# Esquematico.net
KiCad netlist of a schematic drawn in Altium Designer
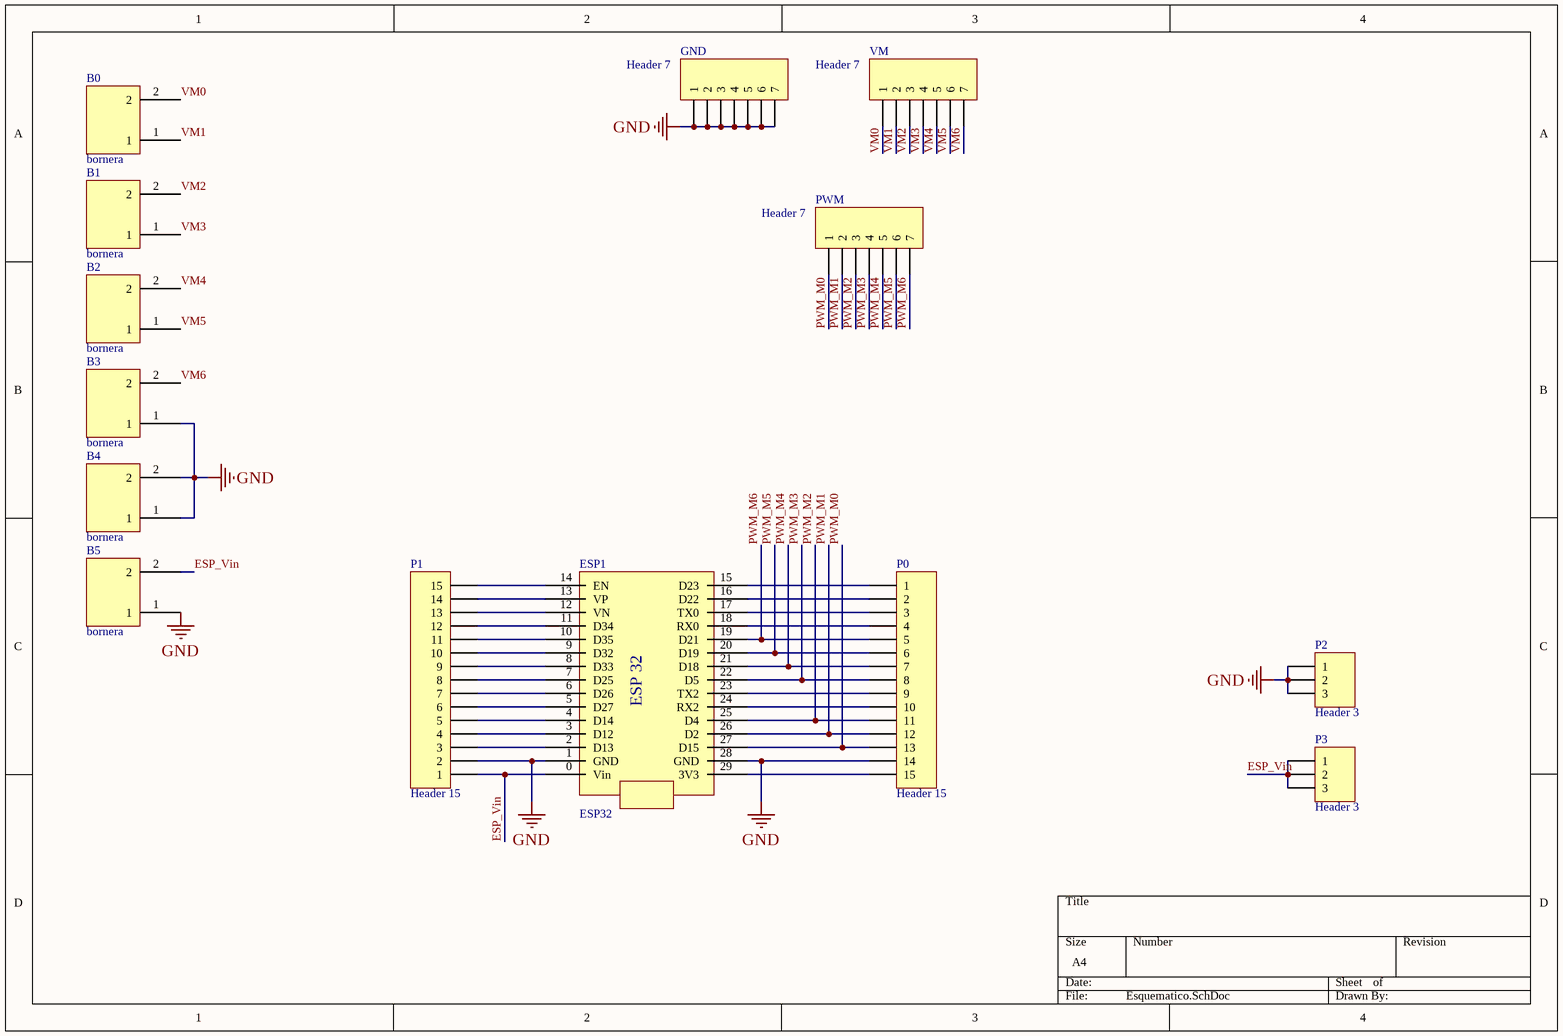
[diagram p0: Esquematico.SchDoc]

(export (version "E")
  (design (tool "Eeschema 10.0.6"))
  (components
    (comp (ref "B0") (value "bornera") (footprint "bornera chica") (libsource (lib "Erick") (part "bornera")))
    (comp (ref "B1") (value "bornera") (footprint "bornera chica") (libsource (lib "Erick") (part "bornera")))
    (comp (ref "B2") (value "bornera") (footprint "bornera chica") (libsource (lib "Erick") (part "bornera")))
    (comp (ref "B3") (value "bornera") (footprint "bornera chica") (libsource (lib "Erick") (part "bornera")))
    (comp (ref "B4") (value "bornera") (footprint "bornera chica") (libsource (lib "Erick") (part "bornera")))
    (comp (ref "B5") (value "bornera") (footprint "bornera chica") (libsource (lib "Erick") (part "bornera")))
    (comp (ref "ESP1") (value "ESP32") (footprint "ESP32") (libsource (lib "Erick") (part "ESP32")))
    (comp (ref "GND")
      (value "Header 7")
      (footprint "Header 7")
      (description "Header, 7-Pin")
      (fields (field (name "PUBLISHER") "Altium Limited"))
      (libsource (lib "hphonglib") (part "Header 7"))
    )
    (comp (ref "P0")
      (value "Header 15")
      (footprint "HDR1X15")
      (description "Header, 15-Pin")
      (fields (field (name "PUBLISHER") "Altium Limited"))
      (libsource (lib "") (part "Header 15_1"))
    )
    (comp (ref "P1")
      (value "Header 15")
      (footprint "HDR1X15")
      (description "Header, 15-Pin")
      (fields (field (name "PUBLISHER") "Altium Limited"))
      (libsource (lib "Miscellaneous Connectors") (part "Header 15"))
    )
    (comp (ref "P2")
      (value "Header 3")
      (footprint "Header 3")
      (description "Header, 3-Pin")
      (fields (field (name "PUBLISHER") "Altium Limited"))
      (libsource (lib "Miscellaneous Connectors") (part "Header 3"))
    )
    (comp (ref "P3")
      (value "Header 3")
      (footprint "Header 3")
      (description "Header, 3-Pin")
      (fields (field (name "PUBLISHER") "Altium Limited"))
      (libsource (lib "Miscellaneous Connectors") (part "Header 3"))
    )
    (comp (ref "PWM")
      (value "Header 7")
      (footprint "Header 7")
      (description "Header, 7-Pin")
      (fields (field (name "PUBLISHER") "Altium Limited"))
      (libsource (lib "hphonglib") (part "Header 7"))
    )
    (comp (ref "VM")
      (value "Header 7")
      (footprint "Header 7")
      (description "Header, 7-Pin")
      (fields (field (name "PUBLISHER") "Altium Limited"))
      (libsource (lib "hphonglib") (part "Header 7"))
    )
  )
  (nets
    (net (code "1") (name "/ESP_Vin") (class "Default")
      (node (ref "B5") (pin "2") (pinfunction "2_2") (pintype "passive"))
      (node (ref "ESP1") (pin "0") (pinfunction "Vin_0") (pintype "passive"))
      (node (ref "P1") (pin "1") (pinfunction "1_1") (pintype "passive"))
      (node (ref "P3") (pin "1") (pinfunction "1_1") (pintype "passive"))
      (node (ref "P3") (pin "2") (pinfunction "2_2") (pintype "passive"))
      (node (ref "P3") (pin "3") (pinfunction "3_3") (pintype "passive"))
    )
    (net (code "2") (name "/PWM_M0") (class "Default")
      (node (ref "ESP1") (pin "27") (pinfunction "D15_27") (pintype "passive"))
      (node (ref "P0") (pin "13") (pinfunction "13_13") (pintype "passive"))
      (node (ref "PWM") (pin "1") (pinfunction "1_1") (pintype "passive"))
    )
    (net (code "3") (name "/PWM_M1") (class "Default")
      (node (ref "ESP1") (pin "26") (pinfunction "D2_26") (pintype "passive"))
      (node (ref "P0") (pin "12") (pinfunction "12_12") (pintype "passive"))
      (node (ref "PWM") (pin "2") (pinfunction "2_2") (pintype "passive"))
    )
    (net (code "4") (name "/PWM_M2") (class "Default")
      (node (ref "ESP1") (pin "25") (pinfunction "D4_25") (pintype "passive"))
      (node (ref "P0") (pin "11") (pinfunction "11_11") (pintype "passive"))
      (node (ref "PWM") (pin "3") (pinfunction "3_3") (pintype "passive"))
    )
    (net (code "5") (name "/PWM_M3") (class "Default")
      (node (ref "ESP1") (pin "22") (pinfunction "D5_22") (pintype "passive"))
      (node (ref "P0") (pin "8") (pinfunction "8_8") (pintype "passive"))
      (node (ref "PWM") (pin "4") (pinfunction "4_4") (pintype "passive"))
    )
    (net (code "6") (name "/PWM_M4") (class "Default")
      (node (ref "ESP1") (pin "21") (pinfunction "D18_21") (pintype "passive"))
      (node (ref "P0") (pin "7") (pinfunction "7_7") (pintype "passive"))
      (node (ref "PWM") (pin "5") (pinfunction "5_5") (pintype "passive"))
    )
    (net (code "7") (name "/PWM_M5") (class "Default")
      (node (ref "ESP1") (pin "20") (pinfunction "D19_20") (pintype "passive"))
      (node (ref "P0") (pin "6") (pinfunction "6_6") (pintype "passive"))
      (node (ref "PWM") (pin "6") (pinfunction "6_6") (pintype "passive"))
    )
    (net (code "8") (name "/PWM_M6") (class "Default")
      (node (ref "ESP1") (pin "19") (pinfunction "D21_19") (pintype "passive"))
      (node (ref "P0") (pin "5") (pinfunction "5_5") (pintype "passive"))
      (node (ref "PWM") (pin "7") (pinfunction "7_7") (pintype "passive"))
    )
    (net (code "9") (name "/VM0") (class "Default")
      (node (ref "B0") (pin "2") (pinfunction "2_2") (pintype "passive"))
      (node (ref "VM") (pin "1") (pinfunction "1_1") (pintype "passive"))
    )
    (net (code "10") (name "/VM1") (class "Default")
      (node (ref "B0") (pin "1") (pinfunction "1_1") (pintype "passive"))
      (node (ref "VM") (pin "2") (pinfunction "2_2") (pintype "passive"))
    )
    (net (code "11") (name "/VM2") (class "Default")
      (node (ref "B1") (pin "2") (pinfunction "2_2") (pintype "passive"))
      (node (ref "VM") (pin "3") (pinfunction "3_3") (pintype "passive"))
    )
    (net (code "12") (name "/VM3") (class "Default")
      (node (ref "B1") (pin "1") (pinfunction "1_1") (pintype "passive"))
      (node (ref "VM") (pin "4") (pinfunction "4_4") (pintype "passive"))
    )
    (net (code "13") (name "/VM4") (class "Default")
      (node (ref "B2") (pin "2") (pinfunction "2_2") (pintype "passive"))
      (node (ref "VM") (pin "5") (pinfunction "5_5") (pintype "passive"))
    )
    (net (code "14") (name "/VM5") (class "Default")
      (node (ref "B2") (pin "1") (pinfunction "1_1") (pintype "passive"))
      (node (ref "VM") (pin "6") (pinfunction "6_6") (pintype "passive"))
    )
    (net (code "15") (name "/VM6") (class "Default")
      (node (ref "B3") (pin "2") (pinfunction "2_2") (pintype "passive"))
      (node (ref "VM") (pin "7") (pinfunction "7_7") (pintype "passive"))
    )
    (net (code "16") (name "GND") (class "Default")
      (node (ref "B3") (pin "1") (pinfunction "1_1") (pintype "passive"))
      (node (ref "B4") (pin "1") (pinfunction "1_1") (pintype "passive"))
      (node (ref "B4") (pin "2") (pinfunction "2_2") (pintype "passive"))
      (node (ref "B5") (pin "1") (pinfunction "1_1") (pintype "passive"))
      (node (ref "ESP1") (pin "1") (pinfunction "GND_1") (pintype "passive"))
      (node (ref "ESP1") (pin "28") (pinfunction "GND_28") (pintype "passive"))
      (node (ref "GND") (pin "1") (pinfunction "1_1") (pintype "passive"))
      (node (ref "GND") (pin "2") (pinfunction "2_2") (pintype "passive"))
      (node (ref "GND") (pin "3") (pinfunction "3_3") (pintype "passive"))
      (node (ref "GND") (pin "4") (pinfunction "4_4") (pintype "passive"))
      (node (ref "GND") (pin "5") (pinfunction "5_5") (pintype "passive"))
      (node (ref "GND") (pin "6") (pinfunction "6_6") (pintype "passive"))
      (node (ref "GND") (pin "7") (pinfunction "7_7") (pintype "passive"))
      (node (ref "P0") (pin "14") (pinfunction "14_14") (pintype "passive"))
      (node (ref "P1") (pin "2") (pinfunction "2_2") (pintype "passive"))
      (node (ref "P2") (pin "1") (pinfunction "1_1") (pintype "passive"))
      (node (ref "P2") (pin "2") (pinfunction "2_2") (pintype "passive"))
      (node (ref "P2") (pin "3") (pinfunction "3_3") (pintype "passive"))
    )
    (net (code "17") (name "Net-(ESP1-3V3)") (class "Default")
      (node (ref "ESP1") (pin "29") (pinfunction "3V3_29") (pintype "passive"))
      (node (ref "P0") (pin "15") (pinfunction "15_15") (pintype "passive"))
    )
    (net (code "18") (name "Net-(ESP1-D12)") (class "Default")
      (node (ref "ESP1") (pin "3") (pinfunction "D12_3") (pintype "passive"))
      (node (ref "P1") (pin "4") (pinfunction "4_4") (pintype "passive"))
    )
    (net (code "19") (name "Net-(ESP1-D13)") (class "Default")
      (node (ref "ESP1") (pin "2") (pinfunction "D13_2") (pintype "passive"))
      (node (ref "P1") (pin "3") (pinfunction "3_3") (pintype "passive"))
    )
    (net (code "20") (name "Net-(ESP1-D14)") (class "Default")
      (node (ref "ESP1") (pin "4") (pinfunction "D14_4") (pintype "passive"))
      (node (ref "P1") (pin "5") (pinfunction "5_5") (pintype "passive"))
    )
    (net (code "21") (name "Net-(ESP1-D22)") (class "Default")
      (node (ref "ESP1") (pin "16") (pinfunction "D22_16") (pintype "passive"))
      (node (ref "P0") (pin "2") (pinfunction "2_2") (pintype "passive"))
    )
    (net (code "22") (name "Net-(ESP1-D23)") (class "Default")
      (node (ref "ESP1") (pin "15") (pinfunction "D23_15") (pintype "passive"))
      (node (ref "P0") (pin "1") (pinfunction "1_1") (pintype "passive"))
    )
    (net (code "23") (name "Net-(ESP1-D25)") (class "Default")
      (node (ref "ESP1") (pin "7") (pinfunction "D25_7") (pintype "passive"))
      (node (ref "P1") (pin "8") (pinfunction "8_8") (pintype "passive"))
    )
    (net (code "24") (name "Net-(ESP1-D26)") (class "Default")
      (node (ref "ESP1") (pin "6") (pinfunction "D26_6") (pintype "passive"))
      (node (ref "P1") (pin "7") (pinfunction "7_7") (pintype "passive"))
    )
    (net (code "25") (name "Net-(ESP1-D27)") (class "Default")
      (node (ref "ESP1") (pin "5") (pinfunction "D27_5") (pintype "passive"))
      (node (ref "P1") (pin "6") (pinfunction "6_6") (pintype "passive"))
    )
    (net (code "26") (name "Net-(ESP1-D32)") (class "Default")
      (node (ref "ESP1") (pin "9") (pinfunction "D32_9") (pintype "passive"))
      (node (ref "P1") (pin "10") (pinfunction "10_10") (pintype "passive"))
    )
    (net (code "27") (name "Net-(ESP1-D33)") (class "Default")
      (node (ref "ESP1") (pin "8") (pinfunction "D33_8") (pintype "passive"))
      (node (ref "P1") (pin "9") (pinfunction "9_9") (pintype "passive"))
    )
    (net (code "28") (name "Net-(ESP1-D34)") (class "Default")
      (node (ref "ESP1") (pin "11") (pinfunction "D34_11") (pintype "passive"))
      (node (ref "P1") (pin "12") (pinfunction "12_12") (pintype "passive"))
    )
    (net (code "29") (name "Net-(ESP1-D35)") (class "Default")
      (node (ref "ESP1") (pin "10") (pinfunction "D35_10") (pintype "passive"))
      (node (ref "P1") (pin "11") (pinfunction "11_11") (pintype "passive"))
    )
    (net (code "30") (name "Net-(ESP1-EN)") (class "Default")
      (node (ref "ESP1") (pin "14") (pinfunction "EN_14") (pintype "passive"))
      (node (ref "P1") (pin "15") (pinfunction "15_15") (pintype "passive"))
    )
    (net (code "31") (name "Net-(ESP1-RX0)") (class "Default")
      (node (ref "ESP1") (pin "18") (pinfunction "RX0_18") (pintype "passive"))
      (node (ref "P0") (pin "4") (pinfunction "4_4") (pintype "passive"))
    )
    (net (code "32") (name "Net-(ESP1-RX2)") (class "Default")
      (node (ref "ESP1") (pin "24") (pinfunction "RX2_24") (pintype "passive"))
      (node (ref "P0") (pin "10") (pinfunction "10_10") (pintype "passive"))
    )
    (net (code "33") (name "Net-(ESP1-TX0)") (class "Default")
      (node (ref "ESP1") (pin "17") (pinfunction "TX0_17") (pintype "passive"))
      (node (ref "P0") (pin "3") (pinfunction "3_3") (pintype "passive"))
    )
    (net (code "34") (name "Net-(ESP1-TX2)") (class "Default")
      (node (ref "ESP1") (pin "23") (pinfunction "TX2_23") (pintype "passive"))
      (node (ref "P0") (pin "9") (pinfunction "9_9") (pintype "passive"))
    )
    (net (code "35") (name "Net-(ESP1-VN)") (class "Default")
      (node (ref "ESP1") (pin "12") (pinfunction "VN_12") (pintype "passive"))
      (node (ref "P1") (pin "13") (pinfunction "13_13") (pintype "passive"))
    )
    (net (code "36") (name "Net-(ESP1-VP)") (class "Default")
      (node (ref "ESP1") (pin "13") (pinfunction "VP_13") (pintype "passive"))
      (node (ref "P1") (pin "14") (pinfunction "14_14") (pintype "passive"))
    )
  )
)
